# LeafCanV002.net
KiCad netlist of a schematic drawn in EAGLE
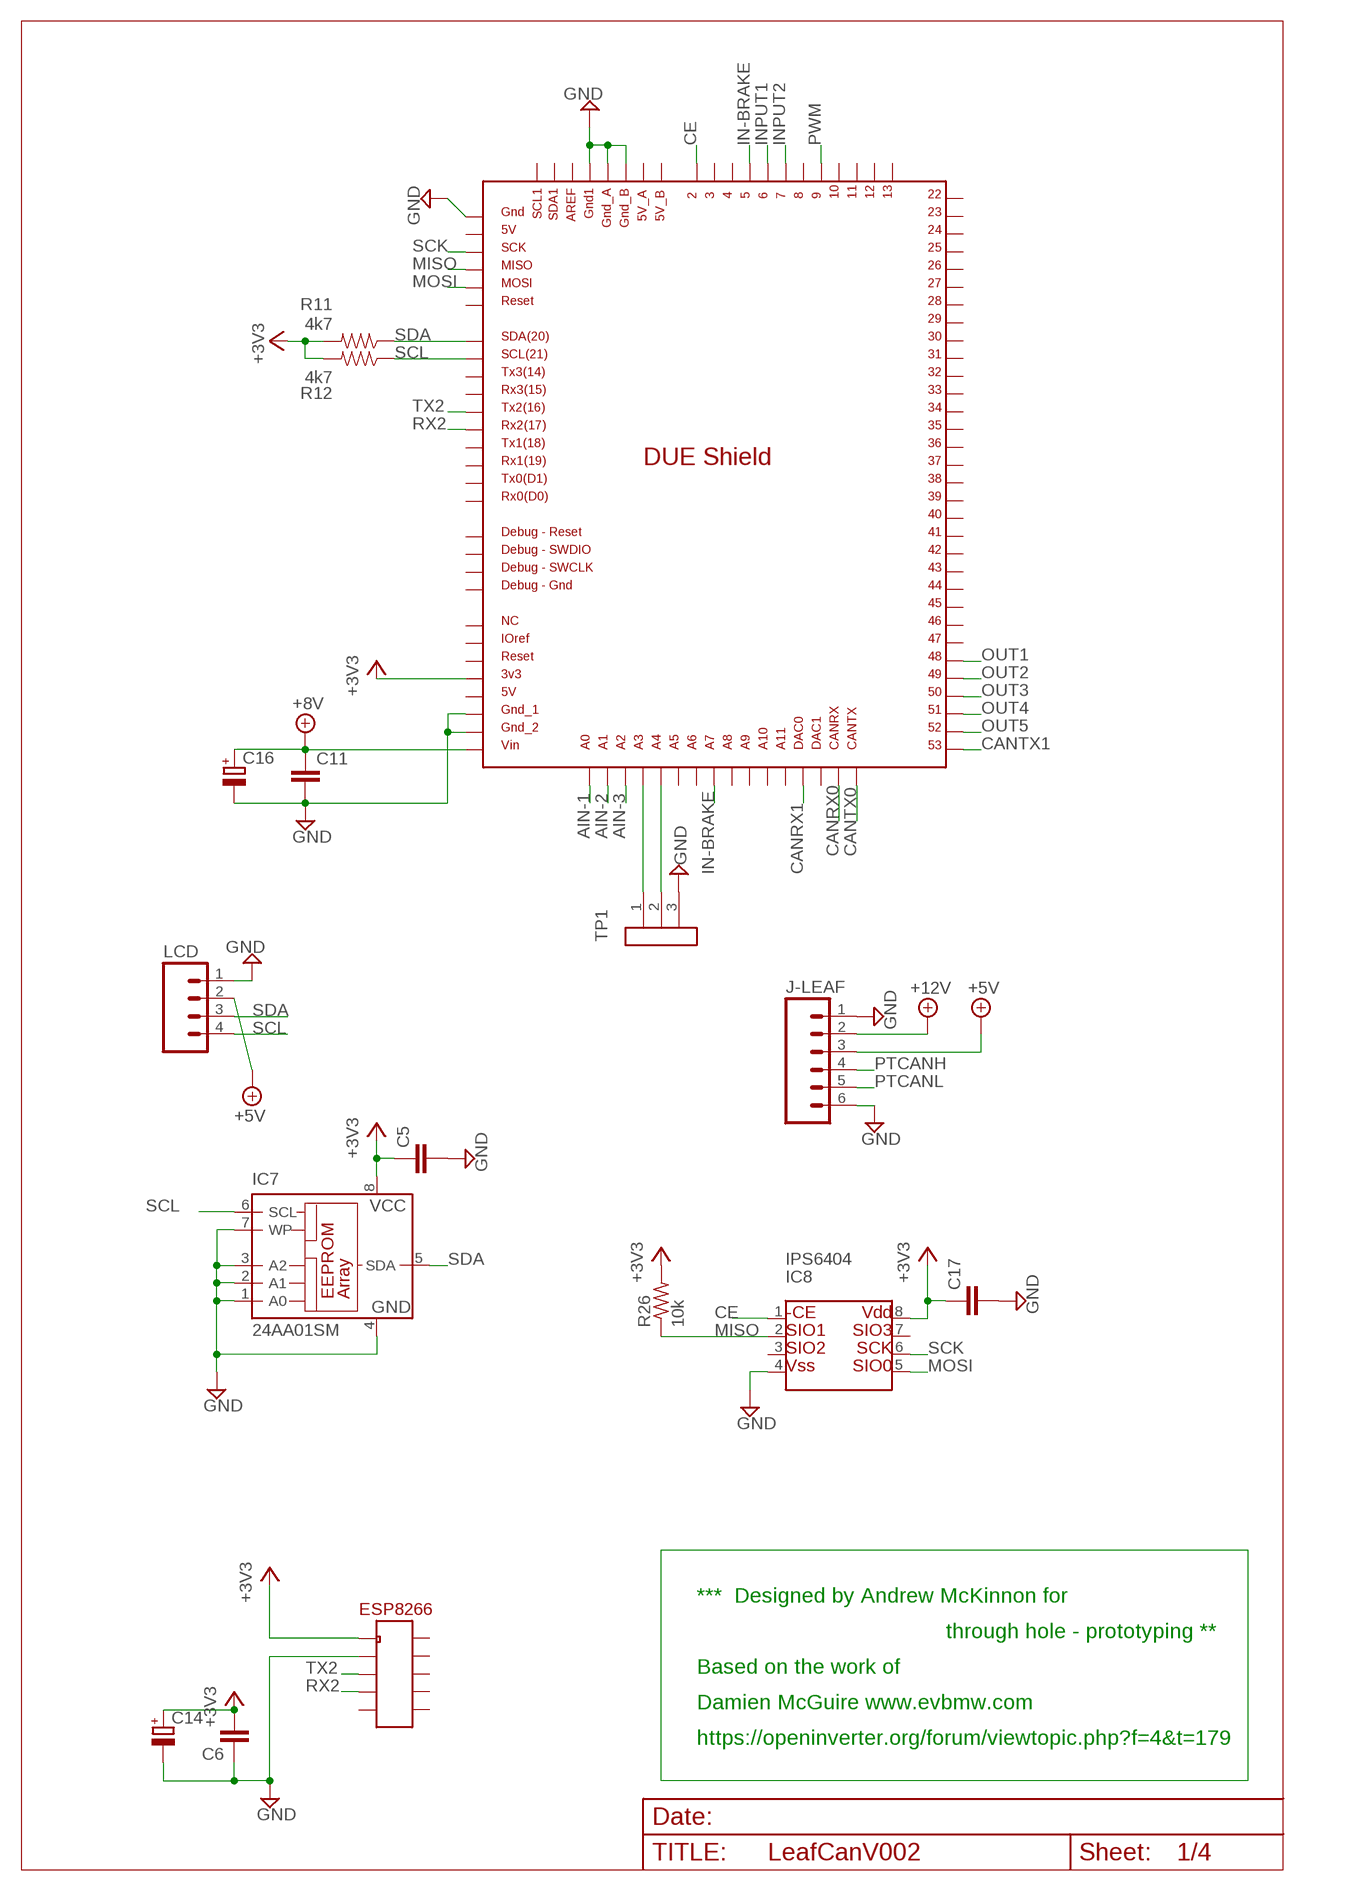
[diagram p0: schematic, sheet 1]
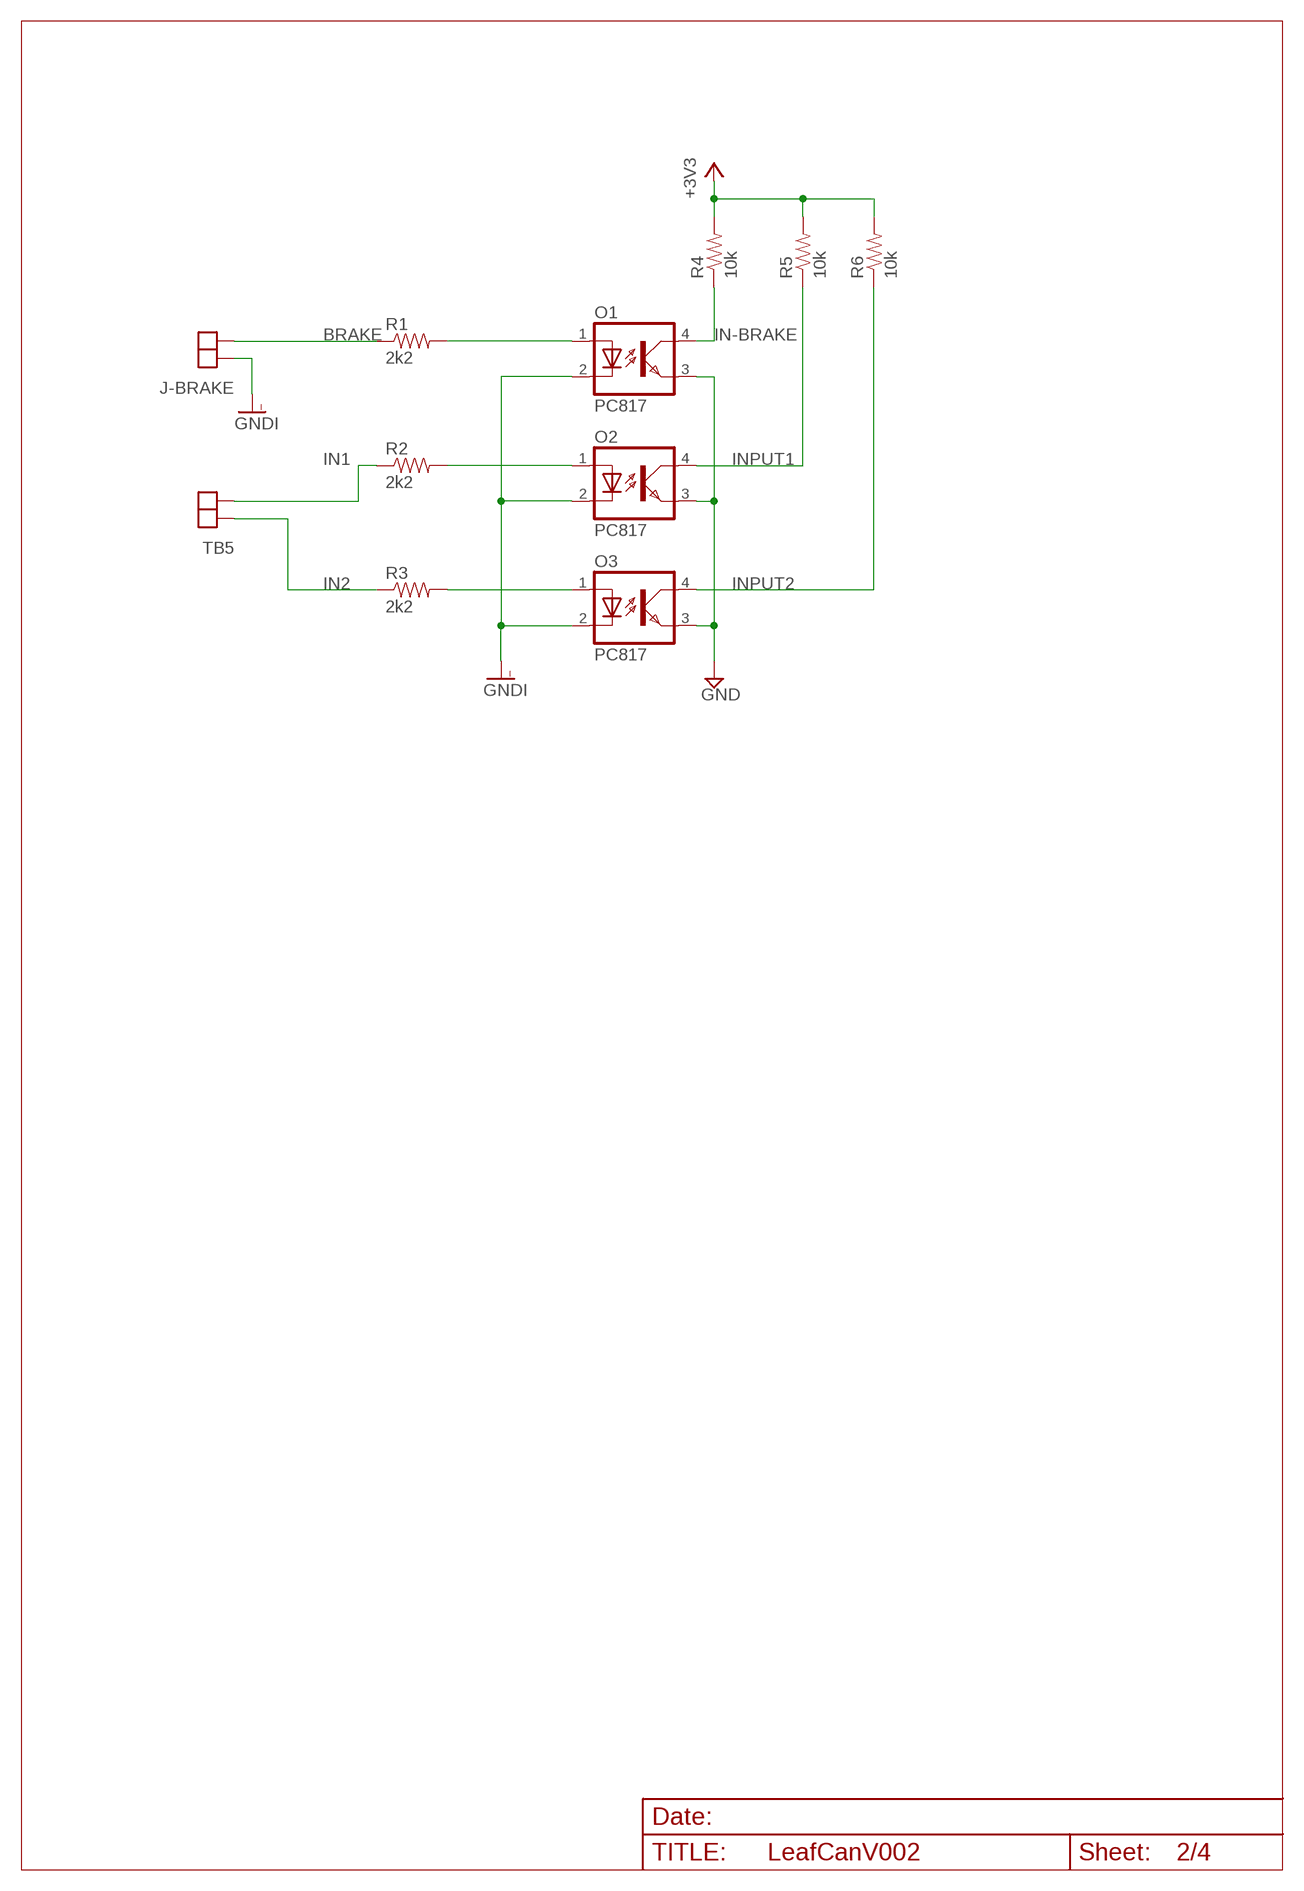
[diagram p1: schematic, sheet 2]
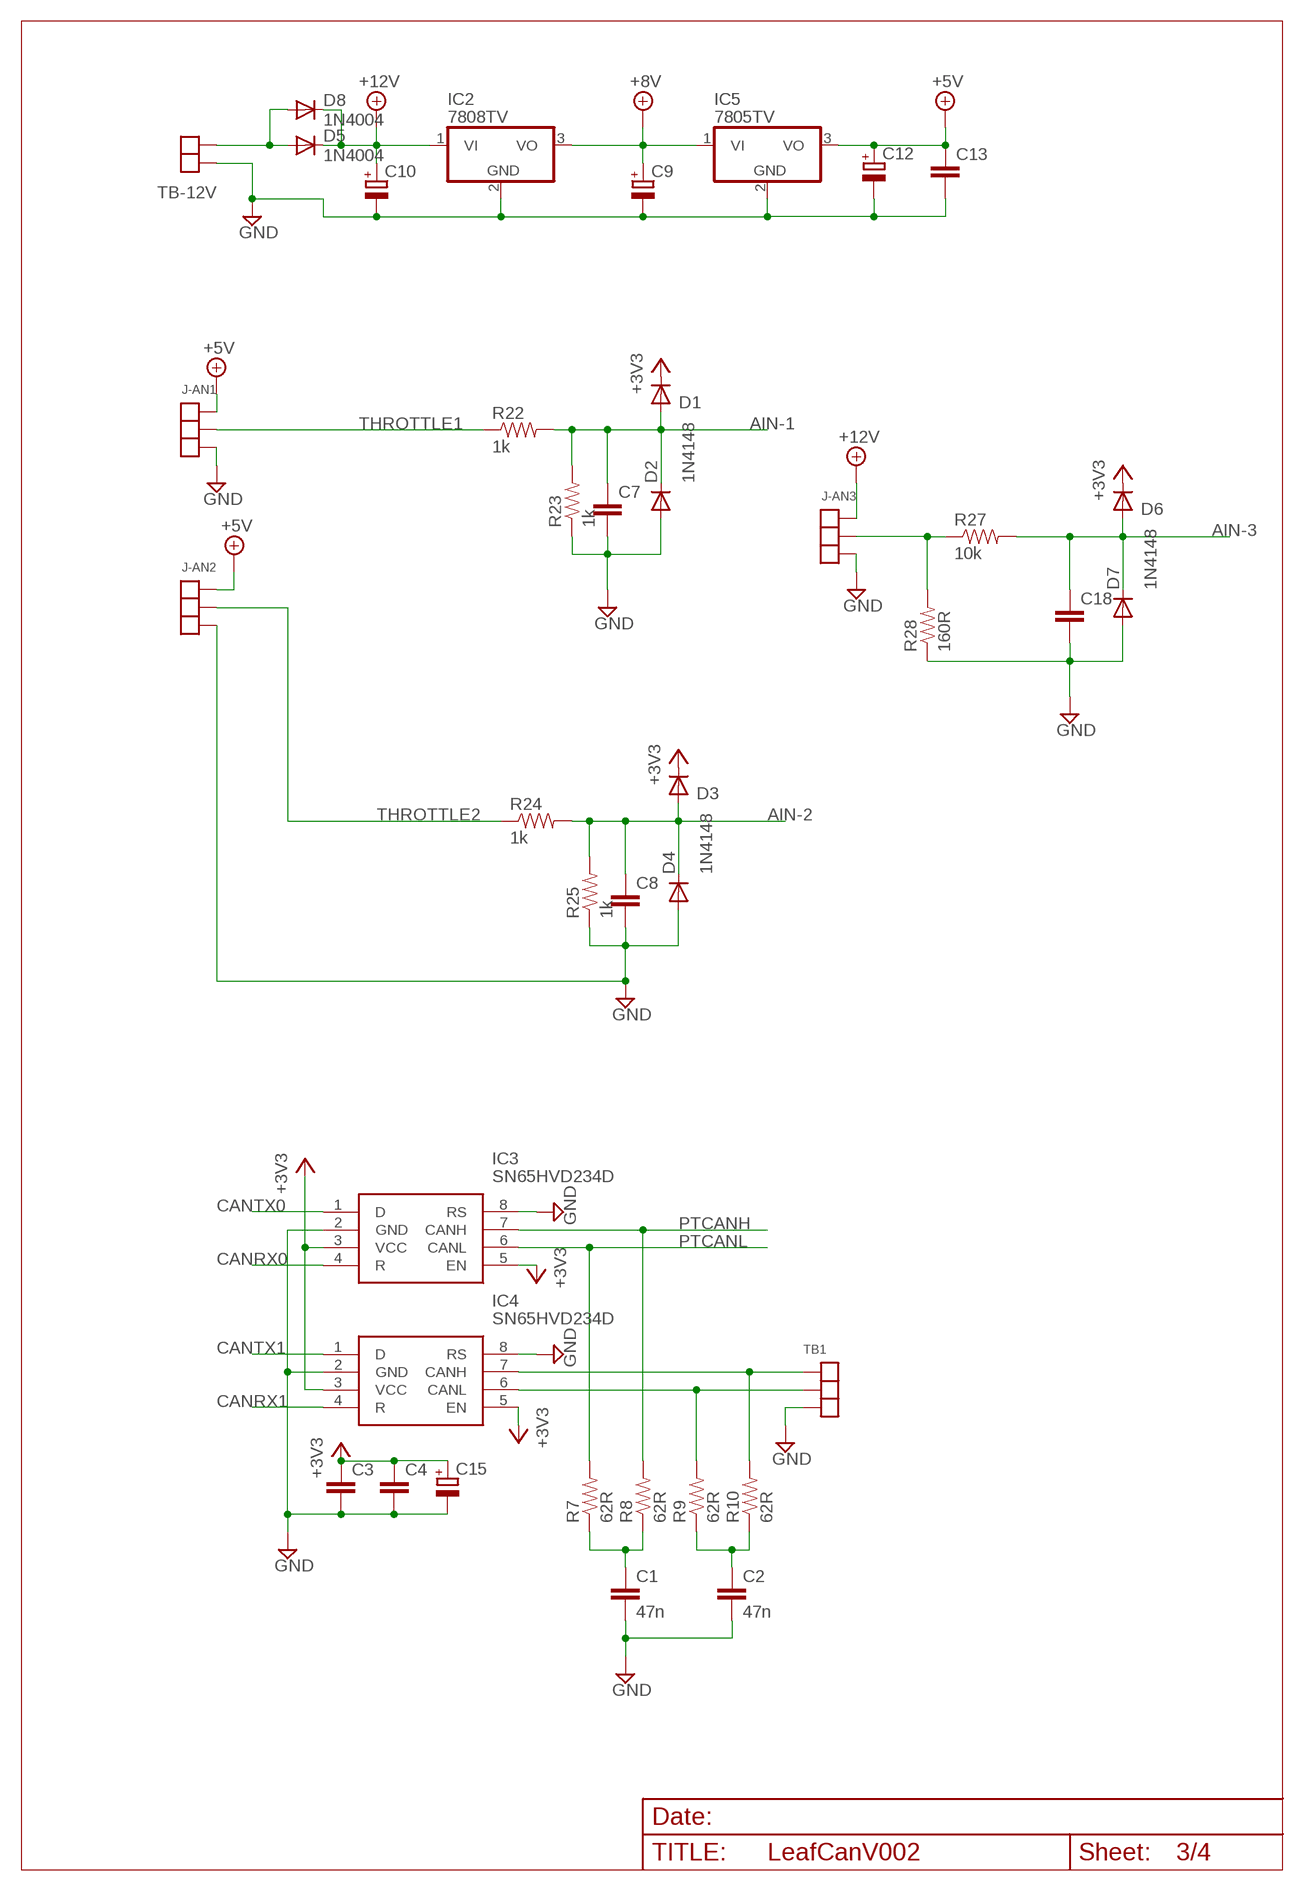
[diagram p2: schematic, sheet 3]
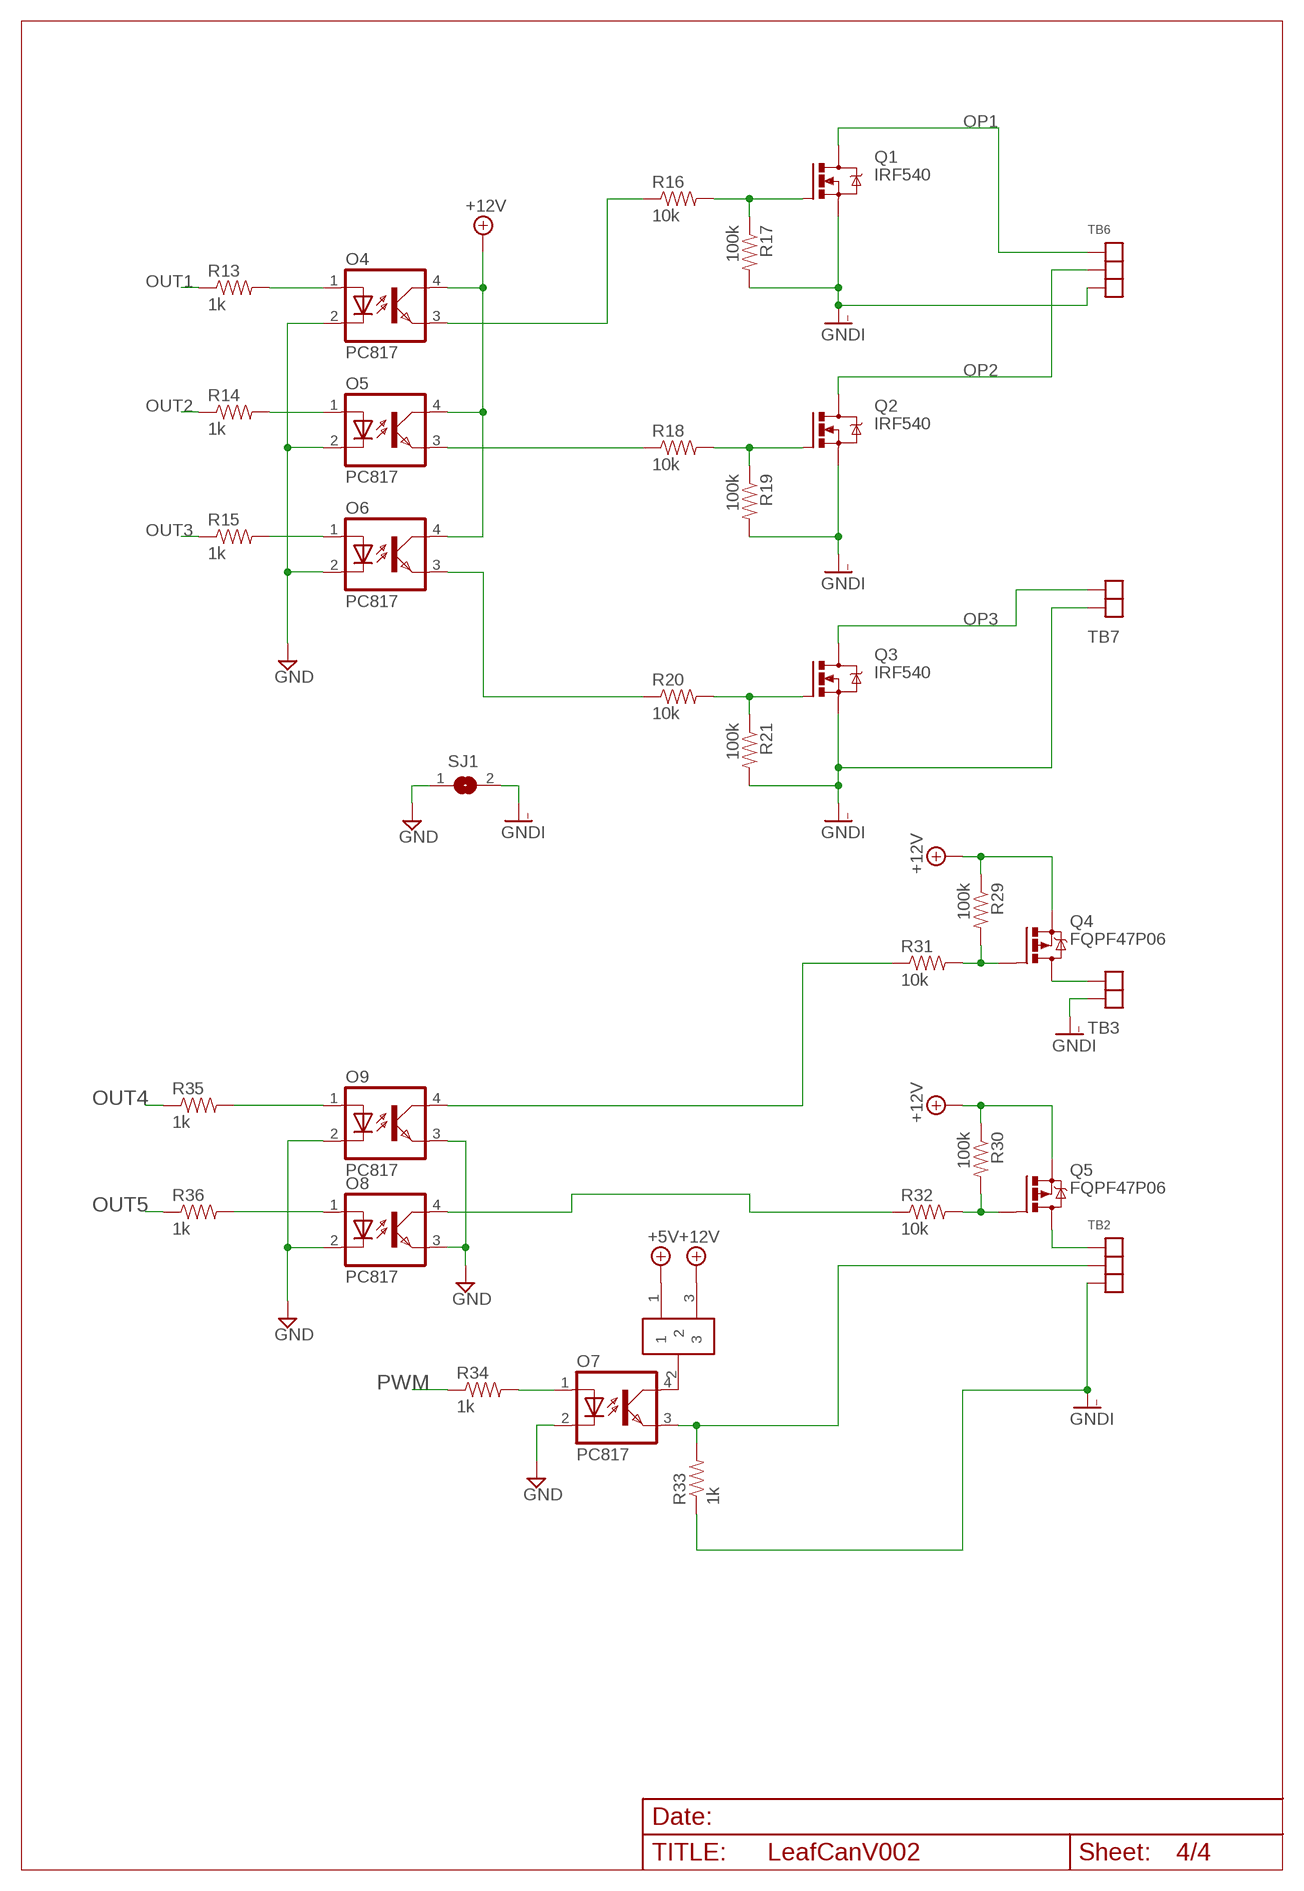
[diagram p3: schematic, sheet 4]

(export (version "E")
  (design (tool "Eeschema 10.0.6"))
  (components
    (comp (ref "C1")
      (value "47n")
      (footprint "eagle-import:C025-030X050")
      (libsource (lib "eagle-import") (part "C-EU025-030X050"))
    )
    (comp (ref "C2")
      (value "47n")
      (footprint "eagle-import:C025-030X050")
      (libsource (lib "eagle-import") (part "C-EU025-030X050"))
    )
    (comp (ref "C3")
      (value "BCAP")
      (footprint "eagle-import:BCAP")
      (libsource (lib "eagle-import") (part "BCAP"))
    )
    (comp (ref "C4")
      (value "BCAP")
      (footprint "eagle-import:BCAP")
      (libsource (lib "eagle-import") (part "BCAP"))
    )
    (comp (ref "C7")
      (value "BCAP")
      (footprint "eagle-import:BCAP")
      (libsource (lib "eagle-import") (part "BCAP"))
    )
    (comp (ref "C8")
      (value "BCAP")
      (footprint "eagle-import:BCAP")
      (libsource (lib "eagle-import") (part "BCAP"))
    )
    (comp (ref "C9")
      (value "C-RB200100")
      (footprint "eagle-import:CPOL-RADIAL-10UF-25V")
      (libsource (lib "eagle-import") (part "C-RB200100"))
    )
    (comp (ref "C10")
      (value "CPOL-EUE7.5-18")
      (footprint "eagle-import:E7,5-18")
      (libsource (lib "eagle-import") (part "CPOL-EUE7.5-18"))
    )
    (comp (ref "C12")
      (value "C-RB200100")
      (footprint "eagle-import:CPOL-RADIAL-10UF-25V")
      (libsource (lib "eagle-import") (part "C-RB200100"))
    )
    (comp (ref "C13")
      (value "BCAP")
      (footprint "eagle-import:BCAP")
      (libsource (lib "eagle-import") (part "BCAP"))
    )
    (comp (ref "C15")
      (value "C-RB200100")
      (footprint "eagle-import:CPOL-RADIAL-10UF-25V")
      (libsource (lib "eagle-import") (part "Andrew Passive_C-RB200100"))
    )
    (comp (ref "C18")
      (value "BCAP")
      (footprint "eagle-import:BCAP")
      (libsource (lib "eagle-import") (part "BCAP"))
    )
    (comp (ref "D1")
      (value "1N4148")
      (footprint "eagle-import:D3")
      (libsource (lib "eagle-import") (part "1N4148DO35-7"))
    )
    (comp (ref "D2")
      (value "1N4148")
      (footprint "eagle-import:D3")
      (libsource (lib "eagle-import") (part "1N4148DO35-7"))
    )
    (comp (ref "D3")
      (value "1N4148")
      (footprint "eagle-import:D3")
      (libsource (lib "eagle-import") (part "1N4148DO35-7"))
    )
    (comp (ref "D4")
      (value "1N4148")
      (footprint "eagle-import:D3")
      (libsource (lib "eagle-import") (part "1N4148DO35-7"))
    )
    (comp (ref "D5")
      (value "1N4004")
      (footprint "eagle-import:DO41-10")
      (libsource (lib "eagle-import") (part "1N4004"))
    )
    (comp (ref "D6")
      (value "1N4148")
      (footprint "eagle-import:D3")
      (libsource (lib "eagle-import") (part "1N4148DO35-7"))
    )
    (comp (ref "D7")
      (value "1N4148")
      (footprint "eagle-import:D3")
      (libsource (lib "eagle-import") (part "1N4148DO35-7"))
    )
    (comp (ref "D8")
      (value "1N4004")
      (footprint "eagle-import:DO41-10")
      (libsource (lib "eagle-import") (part "1N4004"))
    )
    (comp (ref "IC2")
      (value "7808TV")
      (footprint "eagle-import:TO220V")
      (libsource (lib "eagle-import") (part "78TV08"))
    )
    (comp (ref "IC3")
      (value "SN65HVD234D")
      (footprint "eagle-import:SOIC127P600X175-8N")
      (fields
        (field (name "MOUSER_PART_NUMBER") "595-SN65HVD234D")
        (field (name "RS_PART_NUMBER") "6624315P")
      )
      (libsource (lib "eagle-import") (part "SN65HVD234D"))
    )
    (comp (ref "IC4")
      (value "SN65HVD234D")
      (footprint "eagle-import:SOIC127P600X175-8N")
      (fields
        (field (name "MOUSER_PART_NUMBER") "595-SN65HVD234D")
        (field (name "RS_PART_NUMBER") "6624315P")
      )
      (libsource (lib "eagle-import") (part "SN65HVD234D"))
    )
    (comp (ref "IC5")
      (value "7805TV")
      (footprint "eagle-import:TO220V")
      (libsource (lib "eagle-import") (part "78TV05"))
    )
    (comp (ref "J-AN1")
      (value "TB3381V")
      (footprint "eagle-import:TB-KF2EDG381-3-V")
      (libsource (lib "eagle-import") (part "TB3381V"))
    )
    (comp (ref "J-AN2")
      (value "TB3381V")
      (footprint "eagle-import:TB-KF2EDG381-3-V")
      (libsource (lib "eagle-import") (part "TB3381V"))
    )
    (comp (ref "J-AN3")
      (value "TB3381V")
      (footprint "eagle-import:TB-KF2EDG381-3-V")
      (libsource (lib "eagle-import") (part "TB3381V"))
    )
    (comp (ref "R7")
      (value "62R")
      (footprint "eagle-import:AXIAL-0.4")
      (libsource (lib "eagle-import") (part "R4"))
    )
    (comp (ref "R8")
      (value "62R")
      (footprint "eagle-import:AXIAL-0.4")
      (libsource (lib "eagle-import") (part "R4"))
    )
    (comp (ref "R9")
      (value "62R")
      (footprint "eagle-import:AXIAL-0.4")
      (libsource (lib "eagle-import") (part "R4"))
    )
    (comp (ref "R10")
      (value "62R")
      (footprint "eagle-import:AXIAL-0.4")
      (libsource (lib "eagle-import") (part "R4"))
    )
    (comp (ref "R22")
      (value "1k")
      (footprint "eagle-import:AXIAL-0.4")
      (libsource (lib "eagle-import") (part "R4"))
    )
    (comp (ref "R23")
      (value "1k")
      (footprint "eagle-import:AXIAL-0.4")
      (libsource (lib "eagle-import") (part "R4"))
    )
    (comp (ref "R24")
      (value "1k")
      (footprint "eagle-import:AXIAL-0.4")
      (libsource (lib "eagle-import") (part "R4"))
    )
    (comp (ref "R25")
      (value "1k")
      (footprint "eagle-import:AXIAL-0.4")
      (libsource (lib "eagle-import") (part "R4"))
    )
    (comp (ref "R27")
      (value "10k")
      (footprint "eagle-import:AXIAL-0.4")
      (libsource (lib "eagle-import") (part "R4"))
    )
    (comp (ref "R28")
      (value "160R")
      (footprint "eagle-import:AXIAL-0.4")
      (libsource (lib "eagle-import") (part "R4"))
    )
    (comp (ref "TB-12V")
      (value "TB2381")
      (footprint "eagle-import:TB-KF2EDG381-2P")
      (libsource (lib "eagle-import") (part "TB2381"))
    )
    (comp (ref "TB1")
      (value "TB3381V")
      (footprint "eagle-import:TB-KF2EDG381-3-V")
      (libsource (lib "eagle-import") (part "TB3381V"))
    )
    (comp (ref "JP1")
      (value "JP1X3")
      (footprint "eagle-import:JP1X3")
      (libsource (lib "eagle-import") (part "JP1X3"))
    )
    (comp (ref "O4")
      (value "PC817")
      (footprint "eagle-import:DIL04")
      (fields (field (name "MPN") "PC817X4J000F"))
      (libsource (lib "eagle-import") (part "PC817"))
    )
    (comp (ref "O5")
      (value "PC817")
      (footprint "eagle-import:DIL04")
      (fields (field (name "MPN") "PC817X4J000F"))
      (libsource (lib "eagle-import") (part "PC817"))
    )
    (comp (ref "O6")
      (value "PC817")
      (footprint "eagle-import:DIL04")
      (fields (field (name "MPN") "PC817X4J000F"))
      (libsource (lib "eagle-import") (part "PC817"))
    )
    (comp (ref "O7")
      (value "PC817")
      (footprint "eagle-import:DIL04")
      (fields (field (name "MPN") "PC817X4J000F"))
      (libsource (lib "eagle-import") (part "PC817"))
    )
    (comp (ref "O8")
      (value "PC817")
      (footprint "eagle-import:DIL04")
      (fields
        (field (name "MPN") "PC817X4J000F")
        (field (name "MPN_1") "PC817X4J000F")
        (field (name "OC_FARNELL") "9707727")
        (field (name "OC_NEWARK") "97K7059")
      )
      (libsource (lib "eagle-import") (part "PC817"))
    )
    (comp (ref "O9")
      (value "PC817")
      (footprint "eagle-import:DIL04")
      (fields
        (field (name "MPN") "PC817X4J000F")
        (field (name "MPN_1") "PC817X4J000F")
        (field (name "OC_FARNELL") "9707727")
        (field (name "OC_NEWARK") "97K7059")
      )
      (libsource (lib "eagle-import") (part "PC817"))
    )
    (comp (ref "Q1")
      (value "IRF540")
      (footprint "eagle-import:TO220BV")
      (libsource (lib "eagle-import") (part "IRF540"))
    )
    (comp (ref "Q2")
      (value "IRF540")
      (footprint "eagle-import:TO220BV")
      (libsource (lib "eagle-import") (part "IRF540"))
    )
    (comp (ref "Q3")
      (value "IRF540")
      (footprint "eagle-import:TO220BV")
      (libsource (lib "eagle-import") (part "IRF540"))
    )
    (comp (ref "Q4")
      (value "FQPF47P06")
      (footprint "eagle-import:TO220BV")
      (libsource (lib "eagle-import") (part "MOSFET-PCHFQPF47P06"))
    )
    (comp (ref "Q5")
      (value "FQPF47P06")
      (footprint "eagle-import:TO220BV")
      (libsource (lib "eagle-import") (part "MOSFET-PCHFQPF47P06"))
    )
    (comp (ref "R13")
      (value "1k")
      (footprint "eagle-import:AXIAL-0.4")
      (libsource (lib "eagle-import") (part "R4"))
    )
    (comp (ref "R14")
      (value "1k")
      (footprint "eagle-import:AXIAL-0.4")
      (libsource (lib "eagle-import") (part "R4"))
    )
    (comp (ref "R15")
      (value "1k")
      (footprint "eagle-import:AXIAL-0.4")
      (libsource (lib "eagle-import") (part "R4"))
    )
    (comp (ref "R16")
      (value "10k")
      (footprint "eagle-import:AXIAL-0.4")
      (libsource (lib "eagle-import") (part "R4"))
    )
    (comp (ref "R17")
      (value "100k")
      (footprint "eagle-import:AXIAL-0.4")
      (libsource (lib "eagle-import") (part "R4"))
    )
    (comp (ref "R18")
      (value "10k")
      (footprint "eagle-import:AXIAL-0.4")
      (libsource (lib "eagle-import") (part "R4"))
    )
    (comp (ref "R19")
      (value "100k")
      (footprint "eagle-import:AXIAL-0.4")
      (libsource (lib "eagle-import") (part "R4"))
    )
    (comp (ref "R20")
      (value "10k")
      (footprint "eagle-import:AXIAL-0.4")
      (libsource (lib "eagle-import") (part "R4"))
    )
    (comp (ref "R21")
      (value "100k")
      (footprint "eagle-import:AXIAL-0.4")
      (libsource (lib "eagle-import") (part "R4"))
    )
    (comp (ref "R29")
      (value "100k")
      (footprint "eagle-import:AXIAL-0.4")
      (libsource (lib "eagle-import") (part "R4"))
    )
    (comp (ref "R30")
      (value "100k")
      (footprint "eagle-import:AXIAL-0.4")
      (libsource (lib "eagle-import") (part "R4"))
    )
    (comp (ref "R31")
      (value "10k")
      (footprint "eagle-import:AXIAL-0.4")
      (libsource (lib "eagle-import") (part "R4"))
    )
    (comp (ref "R32")
      (value "10k")
      (footprint "eagle-import:AXIAL-0.4")
      (libsource (lib "eagle-import") (part "R4"))
    )
    (comp (ref "R33")
      (value "1k")
      (footprint "eagle-import:AXIAL-0.4")
      (libsource (lib "eagle-import") (part "R4"))
    )
    (comp (ref "R34")
      (value "1k")
      (footprint "eagle-import:AXIAL-0.4")
      (libsource (lib "eagle-import") (part "R4"))
    )
    (comp (ref "R35")
      (value "1k")
      (footprint "eagle-import:AXIAL-0.4")
      (libsource (lib "eagle-import") (part "R4"))
    )
    (comp (ref "R36")
      (value "1k")
      (footprint "eagle-import:AXIAL-0.4")
      (libsource (lib "eagle-import") (part "R4"))
    )
    (comp (ref "SJ1") (value "SJ") (footprint "eagle-import:SJ") (libsource (lib "eagle-import") (part "SJ")))
    (comp (ref "TB2")
      (value "TB3381")
      (footprint "eagle-import:TB-KF2EDG381-3P")
      (libsource (lib "eagle-import") (part "TB3381"))
    )
    (comp (ref "TB3")
      (value "TB2381")
      (footprint "eagle-import:TB-KF2EDG381-2P")
      (libsource (lib "eagle-import") (part "TB2381"))
    )
    (comp (ref "TB6")
      (value "TB3381")
      (footprint "eagle-import:TB-KF2EDG381-3P")
      (libsource (lib "eagle-import") (part "TB3381"))
    )
    (comp (ref "TB7")
      (value "TB2381")
      (footprint "eagle-import:TB-KF2EDG381-2P")
      (libsource (lib "eagle-import") (part "TB2381"))
    )
    (comp (ref "J-BRAKE")
      (value "TB2381")
      (footprint "eagle-import:TB-KF2EDG381-2P")
      (libsource (lib "eagle-import") (part "TB2381"))
    )
    (comp (ref "O1")
      (value "PC817")
      (footprint "eagle-import:DIL04")
      (fields (field (name "MPN") "PC817X4J000F"))
      (libsource (lib "eagle-import") (part "PC817"))
    )
    (comp (ref "O2")
      (value "PC817")
      (footprint "eagle-import:DIL04")
      (fields (field (name "MPN") "PC817X4J000F"))
      (libsource (lib "eagle-import") (part "PC817"))
    )
    (comp (ref "O3")
      (value "PC817")
      (footprint "eagle-import:DIL04")
      (fields (field (name "MPN") "PC817X4J000F"))
      (libsource (lib "eagle-import") (part "PC817"))
    )
    (comp (ref "R1")
      (value "2k2")
      (footprint "eagle-import:AXIAL-0.4")
      (libsource (lib "eagle-import") (part "R4"))
    )
    (comp (ref "R2")
      (value "2k2")
      (footprint "eagle-import:AXIAL-0.4")
      (libsource (lib "eagle-import") (part "R4"))
    )
    (comp (ref "R3")
      (value "2k2")
      (footprint "eagle-import:AXIAL-0.4")
      (libsource (lib "eagle-import") (part "R4"))
    )
    (comp (ref "R4")
      (value "10k")
      (footprint "eagle-import:AXIAL-0.4")
      (libsource (lib "eagle-import") (part "R4"))
    )
    (comp (ref "R5")
      (value "10k")
      (footprint "eagle-import:AXIAL-0.4")
      (libsource (lib "eagle-import") (part "R4"))
    )
    (comp (ref "R6")
      (value "10k")
      (footprint "eagle-import:AXIAL-0.4")
      (libsource (lib "eagle-import") (part "R4"))
    )
    (comp (ref "TB5")
      (value "TB2381")
      (footprint "eagle-import:TB-KF2EDG381-2P")
      (libsource (lib "eagle-import") (part "TB2381"))
    )
    (comp (ref "C5")
      (value "BCAP")
      (footprint "eagle-import:BCAP")
      (libsource (lib "eagle-import") (part "BCAP"))
    )
    (comp (ref "C6")
      (value "BCAP")
      (footprint "eagle-import:BCAP")
      (libsource (lib "eagle-import") (part "BCAP"))
    )
    (comp (ref "C11")
      (value "BCAP")
      (footprint "eagle-import:BCAP")
      (libsource (lib "eagle-import") (part "BCAP"))
    )
    (comp (ref "C14")
      (value "C-RB200100")
      (footprint "eagle-import:CPOL-RADIAL-10UF-25V")
      (libsource (lib "eagle-import") (part "Andrew Passive_C-RB200100"))
    )
    (comp (ref "C16")
      (value "C-RB200100")
      (footprint "eagle-import:CPOL-RADIAL-10UF-25V")
      (libsource (lib "eagle-import") (part "Andrew Passive_C-RB200100"))
    )
    (comp (ref "C17")
      (value "BCAP")
      (footprint "eagle-import:BCAP")
      (libsource (lib "eagle-import") (part "BCAP"))
    )
    (comp (ref "ESP8266")
      (value "IDC10")
      (footprint "eagle-import:IDC10-SMALL")
      (libsource (lib "eagle-import") (part "IDC10"))
    )
    (comp (ref "IC1")
      (value "DUE(NORMAL)")
      (footprint "eagle-import:DUE(NORMAL)")
      (libsource (lib "eagle-import") (part "DUE(NORMAL)"))
    )
    (comp (ref "IC7")
      (value "24AA01SM")
      (footprint "eagle-import:SO-08M")
      (fields (field (name "MF") "MICROCHIP") (field (name "MPN") "24AA01-I/SN"))
      (libsource (lib "eagle-import") (part "24SMAA01"))
    )
    (comp (ref "IC8")
      (value "IPS6404")
      (footprint "eagle-import:SO-08")
      (libsource (lib "eagle-import") (part "IPS6404"))
    )
    (comp (ref "J-LEAF")
      (value "MO6POL")
      (footprint "eagle-import:MOLEX-6")
      (libsource (lib "eagle-import") (part "MO6POL"))
    )
    (comp (ref "LCD")
      (value "MO4POL")
      (footprint "eagle-import:MOLEX-4")
      (libsource (lib "eagle-import") (part "MO4POL"))
    )
    (comp (ref "R11")
      (value "4k7")
      (footprint "eagle-import:AXIAL-0.4")
      (libsource (lib "eagle-import") (part "R4"))
    )
    (comp (ref "R12")
      (value "4k7")
      (footprint "eagle-import:AXIAL-0.4")
      (libsource (lib "eagle-import") (part "R4"))
    )
    (comp (ref "R26")
      (value "10k")
      (footprint "eagle-import:R1206")
      (libsource (lib "eagle-import") (part "R-US_R1206"))
    )
    (comp (ref "TP1")
      (value "SIL3")
      (footprint "eagle-import:SIL3")
      (libsource (lib "eagle-import") (part "SIL3"))
    )
  )
  (nets
    (net (code "1") (name "+3V3") (class "Default")
      (node (ref "C14") (pin "1") (pinfunction "+_1") (pintype "passive"))
      (node (ref "C15") (pin "1") (pinfunction "+_1") (pintype "passive"))
      (node (ref "C17") (pin "1") (pinfunction "1_1") (pintype "passive"))
      (node (ref "C3") (pin "1") (pinfunction "1_1") (pintype "passive"))
      (node (ref "C4") (pin "1") (pinfunction "1_1") (pintype "passive"))
      (node (ref "C5") (pin "1") (pinfunction "1_1") (pintype "passive"))
      (node (ref "C6") (pin "2") (pinfunction "2_2") (pintype "passive"))
      (node (ref "D1") (pin "C") (pinfunction "C_C") (pintype "passive"))
      (node (ref "D3") (pin "C") (pinfunction "C_C") (pintype "passive"))
      (node (ref "D6") (pin "C") (pinfunction "C_C") (pintype "passive"))
      (node (ref "ESP8266") (pin "1") (pinfunction "1_1") (pintype "bidirectional"))
      (node (ref "IC1") (pin "3V3") (pinfunction "3V3_3V3") (pintype "bidirectional"))
      (node (ref "IC3") (pin "3") (pinfunction "VCC_3") (pintype "bidirectional"))
      (node (ref "IC3") (pin "5") (pinfunction "EN_5") (pintype "bidirectional"))
      (node (ref "IC4") (pin "3") (pinfunction "VCC_3") (pintype "bidirectional"))
      (node (ref "IC4") (pin "5") (pinfunction "EN_5") (pintype "bidirectional"))
      (node (ref "IC7") (pin "8") (pinfunction "VCC_8") (pintype "power_in"))
      (node (ref "IC8") (pin "8") (pinfunction "P$8_8") (pintype "bidirectional"))
      (node (ref "R11") (pin "P$2") (pinfunction "2_P$2") (pintype "passive"))
      (node (ref "R12") (pin "P$2") (pinfunction "2_P$2") (pintype "passive"))
      (node (ref "R26") (pin "2") (pinfunction "2_2") (pintype "passive"))
      (node (ref "R4") (pin "P$2") (pinfunction "2_P$2") (pintype "passive"))
      (node (ref "R5") (pin "P$2") (pinfunction "2_P$2") (pintype "passive"))
      (node (ref "R6") (pin "P$2") (pinfunction "2_P$2") (pintype "passive"))
    )
    (net (code "2") (name "+5V") (class "Default")
      (node (ref "C12") (pin "1") (pinfunction "+_1") (pintype "passive"))
      (node (ref "C13") (pin "1") (pinfunction "1_1") (pintype "passive"))
      (node (ref "IC5") (pin "3") (pinfunction "VO_3") (pintype "passive"))
      (node (ref "J-AN1") (pin "1") (pinfunction "1_1") (pintype "bidirectional"))
      (node (ref "J-AN2") (pin "1") (pinfunction "1_1") (pintype "bidirectional"))
      (node (ref "J-LEAF") (pin "3") (pinfunction "3_3") (pintype "passive"))
      (node (ref "JP1") (pin "1") (pinfunction "1_1") (pintype "bidirectional"))
      (node (ref "LCD") (pin "2") (pinfunction "2_2") (pintype "passive"))
    )
    (net (code "3") (name "+8V") (class "Default")
      (node (ref "C11") (pin "1") (pinfunction "1_1") (pintype "passive"))
      (node (ref "C16") (pin "1") (pinfunction "+_1") (pintype "passive"))
      (node (ref "C9") (pin "1") (pinfunction "+_1") (pintype "passive"))
      (node (ref "IC1") (pin "VIN") (pinfunction "VIN_VIN") (pintype "bidirectional"))
      (node (ref "IC2") (pin "3") (pinfunction "VO_3") (pintype "passive"))
      (node (ref "IC5") (pin "1") (pinfunction "VI_1") (pintype "input"))
    )
    (net (code "4") (name "+12V") (class "Default")
      (node (ref "C10") (pin "+") (pinfunction "+_+") (pintype "passive"))
      (node (ref "D5") (pin "C") (pinfunction "C_C") (pintype "passive"))
      (node (ref "D8") (pin "C") (pinfunction "C_C") (pintype "passive"))
      (node (ref "IC2") (pin "1") (pinfunction "VI_1") (pintype "input"))
      (node (ref "J-AN3") (pin "1") (pinfunction "1_1") (pintype "bidirectional"))
      (node (ref "J-LEAF") (pin "2") (pinfunction "2_2") (pintype "passive"))
      (node (ref "JP1") (pin "3") (pinfunction "3_3") (pintype "bidirectional"))
      (node (ref "O4") (pin "4") (pinfunction "COL_4") (pintype "passive"))
      (node (ref "O5") (pin "4") (pinfunction "COL_4") (pintype "passive"))
      (node (ref "O6") (pin "4") (pinfunction "COL_4") (pintype "passive"))
      (node (ref "Q4") (pin "S") (pinfunction "S_S") (pintype "passive"))
      (node (ref "Q5") (pin "S") (pinfunction "S_S") (pintype "passive"))
      (node (ref "R29") (pin "P$1") (pinfunction "1_P$1") (pintype "passive"))
      (node (ref "R30") (pin "P$1") (pinfunction "1_P$1") (pintype "passive"))
    )
    (net (code "5") (name "AIN-1") (class "Default")
      (node (ref "C7") (pin "1") (pinfunction "1_1") (pintype "passive"))
      (node (ref "D1") (pin "A") (pinfunction "A_A") (pintype "passive"))
      (node (ref "D2") (pin "C") (pinfunction "C_C") (pintype "passive"))
      (node (ref "IC1") (pin "A0") (pinfunction "A0_A0") (pintype "bidirectional"))
      (node (ref "R22") (pin "P$2") (pinfunction "2_P$2") (pintype "passive"))
      (node (ref "R23") (pin "P$2") (pinfunction "2_P$2") (pintype "passive"))
    )
    (net (code "6") (name "AIN-2") (class "Default")
      (node (ref "C8") (pin "1") (pinfunction "1_1") (pintype "passive"))
      (node (ref "D3") (pin "A") (pinfunction "A_A") (pintype "passive"))
      (node (ref "D4") (pin "C") (pinfunction "C_C") (pintype "passive"))
      (node (ref "IC1") (pin "A1") (pinfunction "A1_A1") (pintype "bidirectional"))
      (node (ref "R24") (pin "P$2") (pinfunction "2_P$2") (pintype "passive"))
      (node (ref "R25") (pin "P$2") (pinfunction "2_P$2") (pintype "passive"))
    )
    (net (code "7") (name "AIN-3") (class "Default")
      (node (ref "C18") (pin "1") (pinfunction "1_1") (pintype "passive"))
      (node (ref "D6") (pin "A") (pinfunction "A_A") (pintype "passive"))
      (node (ref "D7") (pin "C") (pinfunction "C_C") (pintype "passive"))
      (node (ref "IC1") (pin "A2") (pinfunction "A2_A2") (pintype "bidirectional"))
      (node (ref "R27") (pin "P$2") (pinfunction "2_P$2") (pintype "passive"))
    )
    (net (code "8") (name "BRAKE") (class "Default")
      (node (ref "J-BRAKE") (pin "1") (pinfunction "1_1") (pintype "bidirectional"))
      (node (ref "R1") (pin "P$1") (pinfunction "1_P$1") (pintype "passive"))
    )
    (net (code "9") (name "CANRX0") (class "Default")
      (node (ref "IC1") (pin "CANRX") (pinfunction "CANRX_CANRX") (pintype "bidirectional"))
      (node (ref "IC3") (pin "4") (pinfunction "R_4") (pintype "bidirectional"))
    )
    (net (code "10") (name "CANRX1") (class "Default")
      (node (ref "IC1") (pin "DAC0") (pinfunction "DAC0_DAC0") (pintype "bidirectional"))
      (node (ref "IC4") (pin "4") (pinfunction "R_4") (pintype "bidirectional"))
    )
    (net (code "11") (name "CANTX0") (class "Default")
      (node (ref "IC1") (pin "CANTX") (pinfunction "CANTX_CANTX") (pintype "bidirectional"))
      (node (ref "IC3") (pin "1") (pinfunction "D_1") (pintype "bidirectional"))
    )
    (net (code "12") (name "CANTX1") (class "Default")
      (node (ref "IC1") (pin "53") (pinfunction "53_53") (pintype "bidirectional"))
      (node (ref "IC4") (pin "1") (pinfunction "D_1") (pintype "bidirectional"))
    )
    (net (code "13") (name "CE") (class "Default")
      (node (ref "IC1") (pin "2") (pinfunction "2_2") (pintype "bidirectional"))
      (node (ref "IC8") (pin "1") (pinfunction "P$1_1") (pintype "bidirectional"))
    )
    (net (code "14") (name "GND") (class "Default")
      (node (ref "C1") (pin "2") (pinfunction "2_2") (pintype "passive"))
      (node (ref "C10") (pin "-") (pinfunction "-_-") (pintype "passive"))
      (node (ref "C11") (pin "2") (pinfunction "2_2") (pintype "passive"))
      (node (ref "C12") (pin "2") (pinfunction "-_2") (pintype "passive"))
      (node (ref "C13") (pin "2") (pinfunction "2_2") (pintype "passive"))
      (node (ref "C14") (pin "2") (pinfunction "-_2") (pintype "passive"))
      (node (ref "C15") (pin "2") (pinfunction "-_2") (pintype "passive"))
      (node (ref "C16") (pin "2") (pinfunction "-_2") (pintype "passive"))
      (node (ref "C17") (pin "2") (pinfunction "2_2") (pintype "passive"))
      (node (ref "C18") (pin "2") (pinfunction "2_2") (pintype "passive"))
      (node (ref "C2") (pin "2") (pinfunction "2_2") (pintype "passive"))
      (node (ref "C3") (pin "2") (pinfunction "2_2") (pintype "passive"))
      (node (ref "C4") (pin "2") (pinfunction "2_2") (pintype "passive"))
      (node (ref "C5") (pin "2") (pinfunction "2_2") (pintype "passive"))
      (node (ref "C6") (pin "1") (pinfunction "1_1") (pintype "passive"))
      (node (ref "C7") (pin "2") (pinfunction "2_2") (pintype "passive"))
      (node (ref "C8") (pin "2") (pinfunction "2_2") (pintype "passive"))
      (node (ref "C9") (pin "2") (pinfunction "-_2") (pintype "passive"))
      (node (ref "D2") (pin "A") (pinfunction "A_A") (pintype "passive"))
      (node (ref "D4") (pin "A") (pinfunction "A_A") (pintype "passive"))
      (node (ref "D7") (pin "A") (pinfunction "A_A") (pintype "passive"))
      (node (ref "ESP8266") (pin "3") (pinfunction "3_3") (pintype "bidirectional"))
      (node (ref "IC1") (pin "5V_ICSP") (pinfunction "5V_ICSP_5V_ICSP") (pintype "bidirectional"))
      (node (ref "IC1") (pin "GND1") (pinfunction "GND1_GND1") (pintype "bidirectional"))
      (node (ref "IC1") (pin "GND_1") (pinfunction "GND_1_GND_1") (pintype "bidirectional"))
      (node (ref "IC1") (pin "GND_2") (pinfunction "GND_2_GND_2") (pintype "bidirectional"))
      (node (ref "IC1") (pin "GND_A") (pinfunction "GND_A_GND_A") (pintype "bidirectional"))
      (node (ref "IC1") (pin "GND_B") (pinfunction "GND_B_GND_B") (pintype "bidirectional"))
      (node (ref "IC2") (pin "2") (pinfunction "GND_2") (pintype "passive"))
      (node (ref "IC3") (pin "2") (pinfunction "GND_2") (pintype "bidirectional"))
      (node (ref "IC3") (pin "8") (pinfunction "RS_8") (pintype "bidirectional"))
      (node (ref "IC4") (pin "2") (pinfunction "GND_2") (pintype "bidirectional"))
      (node (ref "IC4") (pin "8") (pinfunction "RS_8") (pintype "bidirectional"))
      (node (ref "IC5") (pin "2") (pinfunction "GND_2") (pintype "passive"))
      (node (ref "IC7") (pin "1") (pinfunction "A0_1") (pintype "input"))
      (node (ref "IC7") (pin "2") (pinfunction "A1_2") (pintype "input"))
      (node (ref "IC7") (pin "3") (pinfunction "A2_3") (pintype "input"))
      (node (ref "IC7") (pin "4") (pinfunction "GND_4") (pintype "power_in"))
      (node (ref "IC7") (pin "7") (pinfunction "WP_7") (pintype "input"))
      (node (ref "IC8") (pin "4") (pinfunction "P$4_4") (pintype "bidirectional"))
      (node (ref "J-AN1") (pin "3") (pinfunction "3_3") (pintype "bidirectional"))
      (node (ref "J-AN2") (pin "3") (pinfunction "3_3") (pintype "bidirectional"))
      (node (ref "J-AN3") (pin "3") (pinfunction "3_3") (pintype "bidirectional"))
      (node (ref "J-LEAF") (pin "1") (pinfunction "1_1") (pintype "passive"))
      (node (ref "J-LEAF") (pin "6") (pinfunction "6_6") (pintype "passive"))
      (node (ref "LCD") (pin "1") (pinfunction "1_1") (pintype "passive"))
      (node (ref "O1") (pin "3") (pinfunction "EMIT_3") (pintype "passive"))
      (node (ref "O2") (pin "3") (pinfunction "EMIT_3") (pintype "passive"))
      (node (ref "O3") (pin "3") (pinfunction "EMIT_3") (pintype "passive"))
      (node (ref "O4") (pin "2") (pinfunction "C_2") (pintype "passive"))
      (node (ref "O5") (pin "2") (pinfunction "C_2") (pintype "passive"))
      (node (ref "O6") (pin "2") (pinfunction "C_2") (pintype "passive"))
      (node (ref "O7") (pin "2") (pinfunction "C_2") (pintype "passive"))
      (node (ref "O8") (pin "2") (pinfunction "C_2") (pintype "passive"))
      (node (ref "O8") (pin "3") (pinfunction "EMIT_3") (pintype "passive"))
      (node (ref "O9") (pin "2") (pinfunction "C_2") (pintype "passive"))
      (node (ref "O9") (pin "3") (pinfunction "EMIT_3") (pintype "passive"))
      (node (ref "R23") (pin "P$1") (pinfunction "1_P$1") (pintype "passive"))
      (node (ref "R25") (pin "P$1") (pinfunction "1_P$1") (pintype "passive"))
      (node (ref "R28") (pin "P$1") (pinfunction "1_P$1") (pintype "passive"))
      (node (ref "SJ1") (pin "1") (pinfunction "1_1") (pintype "passive"))
      (node (ref "TB-12V") (pin "2") (pinfunction "2_2") (pintype "bidirectional"))
      (node (ref "TB1") (pin "3") (pinfunction "3_3") (pintype "bidirectional"))
      (node (ref "TP1") (pin "3") (pinfunction "P$3_3") (pintype "bidirectional"))
    )
    (net (code "15") (name "GNDI") (class "Default")
      (node (ref "J-BRAKE") (pin "2") (pinfunction "2_2") (pintype "bidirectional"))
      (node (ref "O1") (pin "2") (pinfunction "C_2") (pintype "passive"))
      (node (ref "O2") (pin "2") (pinfunction "C_2") (pintype "passive"))
      (node (ref "O3") (pin "2") (pinfunction "C_2") (pintype "passive"))
      (node (ref "Q1") (pin "S") (pinfunction "S_S") (pintype "passive"))
      (node (ref "Q2") (pin "S") (pinfunction "S_S") (pintype "passive"))
      (node (ref "Q3") (pin "S") (pinfunction "S_S") (pintype "passive"))
      (node (ref "R17") (pin "P$2") (pinfunction "2_P$2") (pintype "passive"))
      (node (ref "R19") (pin "P$2") (pinfunction "2_P$2") (pintype "passive"))
      (node (ref "R21") (pin "P$2") (pinfunction "2_P$2") (pintype "passive"))
      (node (ref "R33") (pin "P$1") (pinfunction "1_P$1") (pintype "passive"))
      (node (ref "SJ1") (pin "2") (pinfunction "2_2") (pintype "passive"))
      (node (ref "TB2") (pin "3") (pinfunction "3_3") (pintype "bidirectional"))
      (node (ref "TB3") (pin "2") (pinfunction "2_2") (pintype "bidirectional"))
      (node (ref "TB6") (pin "3") (pinfunction "3_3") (pintype "bidirectional"))
      (node (ref "TB7") (pin "2") (pinfunction "2_2") (pintype "bidirectional"))
    )
    (net (code "16") (name "IN-BRAKE") (class "Default")
      (node (ref "IC1") (pin "5") (pinfunction "5_5") (pintype "bidirectional"))
      (node (ref "IC1") (pin "A7") (pinfunction "A7_A7") (pintype "bidirectional"))
      (node (ref "O1") (pin "4") (pinfunction "COL_4") (pintype "passive"))
      (node (ref "R4") (pin "P$1") (pinfunction "1_P$1") (pintype "passive"))
    )
    (net (code "17") (name "IN1") (class "Default")
      (node (ref "R2") (pin "P$1") (pinfunction "1_P$1") (pintype "passive"))
      (node (ref "TB5") (pin "1") (pinfunction "1_1") (pintype "bidirectional"))
    )
    (net (code "18") (name "IN2") (class "Default")
      (node (ref "R3") (pin "P$1") (pinfunction "1_P$1") (pintype "passive"))
      (node (ref "TB5") (pin "2") (pinfunction "2_2") (pintype "bidirectional"))
    )
    (net (code "19") (name "INPUT1") (class "Default")
      (node (ref "IC1") (pin "6") (pinfunction "6_6") (pintype "bidirectional"))
      (node (ref "O2") (pin "4") (pinfunction "COL_4") (pintype "passive"))
      (node (ref "R5") (pin "P$1") (pinfunction "1_P$1") (pintype "passive"))
    )
    (net (code "20") (name "INPUT2") (class "Default")
      (node (ref "IC1") (pin "7") (pinfunction "7_7") (pintype "bidirectional"))
      (node (ref "O3") (pin "4") (pinfunction "COL_4") (pintype "passive"))
      (node (ref "R6") (pin "P$1") (pinfunction "1_P$1") (pintype "passive"))
    )
    (net (code "21") (name "MISO") (class "Default")
      (node (ref "IC1") (pin "MISO_ICSP") (pinfunction "MISO_ICSP_MISO_ICSP") (pintype "bidirectional"))
      (node (ref "IC8") (pin "2") (pinfunction "P$2_2") (pintype "bidirectional"))
      (node (ref "R26") (pin "1") (pinfunction "1_1") (pintype "passive"))
    )
    (net (code "22") (name "MOSI") (class "Default")
      (node (ref "IC1") (pin "MOSI_ICSP") (pinfunction "MOSI_ICSP_MOSI_ICSP") (pintype "bidirectional"))
      (node (ref "IC8") (pin "5") (pinfunction "P$5_5") (pintype "bidirectional"))
    )
    (net (code "23") (name "Net-(D5-PadA)") (class "Default")
      (node (ref "D5") (pin "A") (pinfunction "A_A") (pintype "passive"))
      (node (ref "D8") (pin "A") (pinfunction "A_A") (pintype "passive"))
      (node (ref "TB-12V") (pin "1") (pinfunction "1_1") (pintype "bidirectional"))
    )
    (net (code "24") (name "Net-(IC4-CANH)") (class "Default")
      (node (ref "IC4") (pin "7") (pinfunction "CANH_7") (pintype "bidirectional"))
      (node (ref "R10") (pin "P$2") (pinfunction "2_P$2") (pintype "passive"))
      (node (ref "TB1") (pin "1") (pinfunction "1_1") (pintype "bidirectional"))
    )
    (net (code "25") (name "Net-(IC4-CANL)") (class "Default")
      (node (ref "IC4") (pin "6") (pinfunction "CANL_6") (pintype "bidirectional"))
      (node (ref "R9") (pin "P$2") (pinfunction "2_P$2") (pintype "passive"))
      (node (ref "TB1") (pin "2") (pinfunction "2_2") (pintype "bidirectional"))
    )
    (net (code "26") (name "Net-(O1-A)") (class "Default")
      (node (ref "O1") (pin "1") (pinfunction "A_1") (pintype "passive"))
      (node (ref "R1") (pin "P$2") (pinfunction "2_P$2") (pintype "passive"))
    )
    (net (code "27") (name "Net-(O2-A)") (class "Default")
      (node (ref "O2") (pin "1") (pinfunction "A_1") (pintype "passive"))
      (node (ref "R2") (pin "P$2") (pinfunction "2_P$2") (pintype "passive"))
    )
    (net (code "28") (name "Net-(O3-A)") (class "Default")
      (node (ref "O3") (pin "1") (pinfunction "A_1") (pintype "passive"))
      (node (ref "R3") (pin "P$2") (pinfunction "2_P$2") (pintype "passive"))
    )
    (net (code "29") (name "Net-(O4-A)") (class "Default")
      (node (ref "O4") (pin "1") (pinfunction "A_1") (pintype "passive"))
      (node (ref "R13") (pin "P$2") (pinfunction "2_P$2") (pintype "passive"))
    )
    (net (code "30") (name "Net-(O4-EMIT)") (class "Default")
      (node (ref "O4") (pin "3") (pinfunction "EMIT_3") (pintype "passive"))
      (node (ref "R16") (pin "P$1") (pinfunction "1_P$1") (pintype "passive"))
    )
    (net (code "31") (name "Net-(O5-A)") (class "Default")
      (node (ref "O5") (pin "1") (pinfunction "A_1") (pintype "passive"))
      (node (ref "R14") (pin "P$2") (pinfunction "2_P$2") (pintype "passive"))
    )
    (net (code "32") (name "Net-(O5-EMIT)") (class "Default")
      (node (ref "O5") (pin "3") (pinfunction "EMIT_3") (pintype "passive"))
      (node (ref "R18") (pin "P$1") (pinfunction "1_P$1") (pintype "passive"))
    )
    (net (code "33") (name "Net-(O6-A)") (class "Default")
      (node (ref "O6") (pin "1") (pinfunction "A_1") (pintype "passive"))
      (node (ref "R15") (pin "P$2") (pinfunction "2_P$2") (pintype "passive"))
    )
    (net (code "34") (name "Net-(O6-EMIT)") (class "Default")
      (node (ref "O6") (pin "3") (pinfunction "EMIT_3") (pintype "passive"))
      (node (ref "R20") (pin "P$1") (pinfunction "1_P$1") (pintype "passive"))
    )
    (net (code "35") (name "Net-(O7-A)") (class "Default")
      (node (ref "O7") (pin "1") (pinfunction "A_1") (pintype "passive"))
      (node (ref "R34") (pin "P$2") (pinfunction "2_P$2") (pintype "passive"))
    )
    (net (code "36") (name "Net-(O7-COL)") (class "Default")
      (node (ref "JP1") (pin "2") (pinfunction "2_2") (pintype "bidirectional"))
      (node (ref "O7") (pin "4") (pinfunction "COL_4") (pintype "passive"))
    )
    (net (code "37") (name "Net-(O7-EMIT)") (class "Default")
      (node (ref "O7") (pin "3") (pinfunction "EMIT_3") (pintype "passive"))
      (node (ref "R33") (pin "P$2") (pinfunction "2_P$2") (pintype "passive"))
      (node (ref "TB2") (pin "2") (pinfunction "2_2") (pintype "bidirectional"))
    )
    (net (code "38") (name "Net-(O8-A)") (class "Default")
      (node (ref "O8") (pin "1") (pinfunction "A_1") (pintype "passive"))
      (node (ref "R36") (pin "P$2") (pinfunction "2_P$2") (pintype "passive"))
    )
    (net (code "39") (name "Net-(O8-COL)") (class "Default")
      (node (ref "O8") (pin "4") (pinfunction "COL_4") (pintype "passive"))
      (node (ref "R32") (pin "P$1") (pinfunction "1_P$1") (pintype "passive"))
    )
    (net (code "40") (name "Net-(O9-A)") (class "Default")
      (node (ref "O9") (pin "1") (pinfunction "A_1") (pintype "passive"))
      (node (ref "R35") (pin "P$2") (pinfunction "2_P$2") (pintype "passive"))
    )
    (net (code "41") (name "Net-(O9-COL)") (class "Default")
      (node (ref "O9") (pin "4") (pinfunction "COL_4") (pintype "passive"))
      (node (ref "R31") (pin "P$1") (pinfunction "1_P$1") (pintype "passive"))
    )
    (net (code "42") (name "Net-(Q4-PadD)") (class "Default")
      (node (ref "Q4") (pin "D") (pinfunction "D_D") (pintype "passive"))
      (node (ref "TB3") (pin "1") (pinfunction "1_1") (pintype "bidirectional"))
    )
    (net (code "43") (name "Net-(Q5-PadD)") (class "Default")
      (node (ref "Q5") (pin "D") (pinfunction "D_D") (pintype "passive"))
      (node (ref "TB2") (pin "1") (pinfunction "1_1") (pintype "bidirectional"))
    )
    (net (code "44") (name "Net-(R7-1)") (class "Default")
      (node (ref "C1") (pin "1") (pinfunction "1_1") (pintype "passive"))
      (node (ref "R7") (pin "P$1") (pinfunction "1_P$1") (pintype "passive"))
      (node (ref "R8") (pin "P$1") (pinfunction "1_P$1") (pintype "passive"))
    )
    (net (code "45") (name "Net-(R10-1)") (class "Default")
      (node (ref "C2") (pin "1") (pinfunction "1_1") (pintype "passive"))
      (node (ref "R10") (pin "P$1") (pinfunction "1_P$1") (pintype "passive"))
      (node (ref "R9") (pin "P$1") (pinfunction "1_P$1") (pintype "passive"))
    )
    (net (code "46") (name "Net-(R16-2)") (class "Default")
      (node (ref "Q1") (pin "G") (pinfunction "G_G") (pintype "passive"))
      (node (ref "R16") (pin "P$2") (pinfunction "2_P$2") (pintype "passive"))
      (node (ref "R17") (pin "P$1") (pinfunction "1_P$1") (pintype "passive"))
    )
    (net (code "47") (name "Net-(R18-2)") (class "Default")
      (node (ref "Q2") (pin "G") (pinfunction "G_G") (pintype "passive"))
      (node (ref "R18") (pin "P$2") (pinfunction "2_P$2") (pintype "passive"))
      (node (ref "R19") (pin "P$1") (pinfunction "1_P$1") (pintype "passive"))
    )
    (net (code "48") (name "Net-(R20-2)") (class "Default")
      (node (ref "Q3") (pin "G") (pinfunction "G_G") (pintype "passive"))
      (node (ref "R20") (pin "P$2") (pinfunction "2_P$2") (pintype "passive"))
      (node (ref "R21") (pin "P$1") (pinfunction "1_P$1") (pintype "passive"))
    )
    (net (code "49") (name "Net-(R27-1)") (class "Default")
      (node (ref "J-AN3") (pin "2") (pinfunction "2_2") (pintype "bidirectional"))
      (node (ref "R27") (pin "P$1") (pinfunction "1_P$1") (pintype "passive"))
      (node (ref "R28") (pin "P$2") (pinfunction "2_P$2") (pintype "passive"))
    )
    (net (code "50") (name "Net-(R29-2)") (class "Default")
      (node (ref "Q4") (pin "G") (pinfunction "G_G") (pintype "passive"))
      (node (ref "R29") (pin "P$2") (pinfunction "2_P$2") (pintype "passive"))
      (node (ref "R31") (pin "P$2") (pinfunction "2_P$2") (pintype "passive"))
    )
    (net (code "51") (name "Net-(R30-2)") (class "Default")
      (node (ref "Q5") (pin "G") (pinfunction "G_G") (pintype "passive"))
      (node (ref "R30") (pin "P$2") (pinfunction "2_P$2") (pintype "passive"))
      (node (ref "R32") (pin "P$2") (pinfunction "2_P$2") (pintype "passive"))
    )
    (net (code "52") (name "Net-(TP1-P$1)") (class "Default")
      (node (ref "IC1") (pin "A3") (pinfunction "A3_A3") (pintype "bidirectional"))
      (node (ref "TP1") (pin "1") (pinfunction "P$1_1") (pintype "bidirectional"))
    )
    (net (code "53") (name "Net-(TP1-P$2)") (class "Default")
      (node (ref "IC1") (pin "A4") (pinfunction "A4_A4") (pintype "bidirectional"))
      (node (ref "TP1") (pin "2") (pinfunction "P$2_2") (pintype "bidirectional"))
    )
    (net (code "54") (name "OP1") (class "Default")
      (node (ref "Q1") (pin "D") (pinfunction "D_D") (pintype "passive"))
      (node (ref "TB6") (pin "1") (pinfunction "1_1") (pintype "bidirectional"))
    )
    (net (code "55") (name "OP2") (class "Default")
      (node (ref "Q2") (pin "D") (pinfunction "D_D") (pintype "passive"))
      (node (ref "TB6") (pin "2") (pinfunction "2_2") (pintype "bidirectional"))
    )
    (net (code "56") (name "OP3") (class "Default")
      (node (ref "Q3") (pin "D") (pinfunction "D_D") (pintype "passive"))
      (node (ref "TB7") (pin "1") (pinfunction "1_1") (pintype "bidirectional"))
    )
    (net (code "57") (name "OUT1") (class "Default")
      (node (ref "IC1") (pin "48") (pinfunction "48_48") (pintype "bidirectional"))
      (node (ref "R13") (pin "P$1") (pinfunction "1_P$1") (pintype "passive"))
    )
    (net (code "58") (name "OUT2") (class "Default")
      (node (ref "IC1") (pin "49") (pinfunction "49_49") (pintype "bidirectional"))
      (node (ref "R14") (pin "P$1") (pinfunction "1_P$1") (pintype "passive"))
    )
    (net (code "59") (name "OUT3") (class "Default")
      (node (ref "IC1") (pin "50") (pinfunction "50_50") (pintype "bidirectional"))
      (node (ref "R15") (pin "P$1") (pinfunction "1_P$1") (pintype "passive"))
    )
    (net (code "60") (name "OUT4") (class "Default")
      (node (ref "IC1") (pin "51") (pinfunction "51_51") (pintype "bidirectional"))
      (node (ref "R35") (pin "P$1") (pinfunction "1_P$1") (pintype "passive"))
    )
    (net (code "61") (name "OUT5") (class "Default")
      (node (ref "IC1") (pin "52") (pinfunction "52_52") (pintype "bidirectional"))
      (node (ref "R36") (pin "P$1") (pinfunction "1_P$1") (pintype "passive"))
    )
    (net (code "62") (name "PTCANH") (class "Default")
      (node (ref "IC3") (pin "7") (pinfunction "CANH_7") (pintype "bidirectional"))
      (node (ref "J-LEAF") (pin "4") (pinfunction "4_4") (pintype "passive"))
      (node (ref "R8") (pin "P$2") (pinfunction "2_P$2") (pintype "passive"))
    )
    (net (code "63") (name "PTCANL") (class "Default")
      (node (ref "IC3") (pin "6") (pinfunction "CANL_6") (pintype "bidirectional"))
      (node (ref "J-LEAF") (pin "5") (pinfunction "5_5") (pintype "passive"))
      (node (ref "R7") (pin "P$2") (pinfunction "2_P$2") (pintype "passive"))
    )
    (net (code "64") (name "PWM") (class "Default")
      (node (ref "IC1") (pin "9") (pinfunction "9_9") (pintype "bidirectional"))
      (node (ref "R34") (pin "P$1") (pinfunction "1_P$1") (pintype "passive"))
    )
    (net (code "65") (name "RX2") (class "Default")
      (node (ref "ESP8266") (pin "7") (pinfunction "7_7") (pintype "bidirectional"))
      (node (ref "IC1") (pin "RX2") (pinfunction "RX2_RX2") (pintype "bidirectional"))
    )
    (net (code "66") (name "SCK") (class "Default")
      (node (ref "IC1") (pin "SCK_ICSP") (pinfunction "SCK_ICSP_SCK_ICSP") (pintype "bidirectional"))
      (node (ref "IC8") (pin "6") (pinfunction "P$6_6") (pintype "bidirectional"))
    )
    (net (code "67") (name "SCL") (class "Default")
      (node (ref "IC1") (pin "SCL") (pinfunction "SCL_SCL") (pintype "bidirectional"))
      (node (ref "IC7") (pin "6") (pinfunction "SCL_6") (pintype "input"))
      (node (ref "LCD") (pin "4") (pinfunction "4_4") (pintype "passive"))
      (node (ref "R12") (pin "P$1") (pinfunction "1_P$1") (pintype "passive"))
    )
    (net (code "68") (name "SDA") (class "Default")
      (node (ref "IC1") (pin "SDA") (pinfunction "SDA_SDA") (pintype "bidirectional"))
      (node (ref "IC7") (pin "5") (pinfunction "SDA_5") (pintype "bidirectional"))
      (node (ref "LCD") (pin "3") (pinfunction "3_3") (pintype "passive"))
      (node (ref "R11") (pin "P$1") (pinfunction "1_P$1") (pintype "passive"))
    )
    (net (code "69") (name "THROTTLE1") (class "Default")
      (node (ref "J-AN1") (pin "2") (pinfunction "2_2") (pintype "bidirectional"))
      (node (ref "R22") (pin "P$1") (pinfunction "1_P$1") (pintype "passive"))
    )
    (net (code "70") (name "THROTTLE2") (class "Default")
      (node (ref "J-AN2") (pin "2") (pinfunction "2_2") (pintype "bidirectional"))
      (node (ref "R24") (pin "P$1") (pinfunction "1_P$1") (pintype "passive"))
    )
    (net (code "71") (name "TX2") (class "Default")
      (node (ref "ESP8266") (pin "5") (pinfunction "5_5") (pintype "bidirectional"))
      (node (ref "IC1") (pin "TX2") (pinfunction "TX2_TX2") (pintype "bidirectional"))
    )
    (net (code "72") (name "unconnected-(ESP8266-Pad2)") (class "Default")
      (node (ref "ESP8266") (pin "2") (pinfunction "2_2") (pintype "bidirectional"))
    )
    (net (code "73") (name "unconnected-(ESP8266-Pad4)") (class "Default")
      (node (ref "ESP8266") (pin "4") (pinfunction "4_4") (pintype "bidirectional"))
    )
    (net (code "74") (name "unconnected-(ESP8266-Pad6)") (class "Default")
      (node (ref "ESP8266") (pin "6") (pinfunction "6_6") (pintype "bidirectional"))
    )
    (net (code "75") (name "unconnected-(ESP8266-Pad8)") (class "Default")
      (node (ref "ESP8266") (pin "8") (pinfunction "8_8") (pintype "bidirectional"))
    )
    (net (code "76") (name "unconnected-(ESP8266-Pad9)") (class "Default")
      (node (ref "ESP8266") (pin "9") (pinfunction "9_9") (pintype "bidirectional"))
    )
    (net (code "77") (name "unconnected-(ESP8266-Pad10)") (class "Default")
      (node (ref "ESP8266") (pin "10") (pinfunction "10_10") (pintype "bidirectional"))
    )
    (net (code "78") (name "unconnected-(IC1-Pad3)") (class "Default")
      (node (ref "IC1") (pin "3") (pinfunction "3_3") (pintype "bidirectional"))
    )
    (net (code "79") (name "unconnected-(IC1-Pad4)") (class "Default")
      (node (ref "IC1") (pin "4") (pinfunction "4_4") (pintype "bidirectional"))
    )
    (net (code "80") (name "unconnected-(IC1-Pad5V)") (class "Default")
      (node (ref "IC1") (pin "5V") (pinfunction "5V_5V") (pintype "bidirectional"))
    )
    (net (code "81") (name "unconnected-(IC1-Pad5V_A)") (class "Default")
      (node (ref "IC1") (pin "5V_A") (pinfunction "5V_A_5V_A") (pintype "bidirectional"))
    )
    (net (code "82") (name "unconnected-(IC1-Pad5V_B)") (class "Default")
      (node (ref "IC1") (pin "5V_B") (pinfunction "5V_B_5V_B") (pintype "bidirectional"))
    )
    (net (code "83") (name "unconnected-(IC1-Pad8)") (class "Default")
      (node (ref "IC1") (pin "8") (pinfunction "8_8") (pintype "bidirectional"))
    )
    (net (code "84") (name "unconnected-(IC1-Pad10)") (class "Default")
      (node (ref "IC1") (pin "10") (pinfunction "10_10") (pintype "bidirectional"))
    )
    (net (code "85") (name "unconnected-(IC1-Pad11)") (class "Default")
      (node (ref "IC1") (pin "11") (pinfunction "11_11") (pintype "bidirectional"))
    )
    (net (code "86") (name "unconnected-(IC1-Pad12)") (class "Default")
      (node (ref "IC1") (pin "12") (pinfunction "12_12") (pintype "bidirectional"))
    )
    (net (code "87") (name "unconnected-(IC1-Pad13)") (class "Default")
      (node (ref "IC1") (pin "13") (pinfunction "13_13") (pintype "bidirectional"))
    )
    (net (code "88") (name "unconnected-(IC1-Pad22)") (class "Default")
      (node (ref "IC1") (pin "22") (pinfunction "22_22") (pintype "bidirectional"))
    )
    (net (code "89") (name "unconnected-(IC1-Pad23)") (class "Default")
      (node (ref "IC1") (pin "23") (pinfunction "23_23") (pintype "bidirectional"))
    )
    (net (code "90") (name "unconnected-(IC1-Pad24)") (class "Default")
      (node (ref "IC1") (pin "24") (pinfunction "24_24") (pintype "bidirectional"))
    )
    (net (code "91") (name "unconnected-(IC1-Pad25)") (class "Default")
      (node (ref "IC1") (pin "25") (pinfunction "25_25") (pintype "bidirectional"))
    )
    (net (code "92") (name "unconnected-(IC1-Pad26)") (class "Default")
      (node (ref "IC1") (pin "26") (pinfunction "26_26") (pintype "bidirectional"))
    )
    (net (code "93") (name "unconnected-(IC1-Pad27)") (class "Default")
      (node (ref "IC1") (pin "27") (pinfunction "27_27") (pintype "bidirectional"))
    )
    (net (code "94") (name "unconnected-(IC1-Pad28)") (class "Default")
      (node (ref "IC1") (pin "28") (pinfunction "28_28") (pintype "bidirectional"))
    )
    (net (code "95") (name "unconnected-(IC1-Pad29)") (class "Default")
      (node (ref "IC1") (pin "29") (pinfunction "29_29") (pintype "bidirectional"))
    )
    (net (code "96") (name "unconnected-(IC1-Pad30)") (class "Default")
      (node (ref "IC1") (pin "30") (pinfunction "30_30") (pintype "bidirectional"))
    )
    (net (code "97") (name "unconnected-(IC1-Pad31)") (class "Default")
      (node (ref "IC1") (pin "31") (pinfunction "31_31") (pintype "bidirectional"))
    )
    (net (code "98") (name "unconnected-(IC1-Pad32)") (class "Default")
      (node (ref "IC1") (pin "32") (pinfunction "32_32") (pintype "bidirectional"))
    )
    (net (code "99") (name "unconnected-(IC1-Pad33)") (class "Default")
      (node (ref "IC1") (pin "33") (pinfunction "33_33") (pintype "bidirectional"))
    )
    (net (code "100") (name "unconnected-(IC1-Pad34)") (class "Default")
      (node (ref "IC1") (pin "34") (pinfunction "34_34") (pintype "bidirectional"))
    )
    (net (code "101") (name "unconnected-(IC1-Pad35)") (class "Default")
      (node (ref "IC1") (pin "35") (pinfunction "35_35") (pintype "bidirectional"))
    )
    (net (code "102") (name "unconnected-(IC1-Pad36)") (class "Default")
      (node (ref "IC1") (pin "36") (pinfunction "36_36") (pintype "bidirectional"))
    )
    (net (code "103") (name "unconnected-(IC1-Pad37)") (class "Default")
      (node (ref "IC1") (pin "37") (pinfunction "37_37") (pintype "bidirectional"))
    )
    (net (code "104") (name "unconnected-(IC1-Pad38)") (class "Default")
      (node (ref "IC1") (pin "38") (pinfunction "38_38") (pintype "bidirectional"))
    )
    (net (code "105") (name "unconnected-(IC1-Pad39)") (class "Default")
      (node (ref "IC1") (pin "39") (pinfunction "39_39") (pintype "bidirectional"))
    )
    (net (code "106") (name "unconnected-(IC1-Pad40)") (class "Default")
      (node (ref "IC1") (pin "40") (pinfunction "40_40") (pintype "bidirectional"))
    )
    (net (code "107") (name "unconnected-(IC1-Pad41)") (class "Default")
      (node (ref "IC1") (pin "41") (pinfunction "41_41") (pintype "bidirectional"))
    )
    (net (code "108") (name "unconnected-(IC1-Pad42)") (class "Default")
      (node (ref "IC1") (pin "42") (pinfunction "42_42") (pintype "bidirectional"))
    )
    (net (code "109") (name "unconnected-(IC1-Pad43)") (class "Default")
      (node (ref "IC1") (pin "43") (pinfunction "43_43") (pintype "bidirectional"))
    )
    (net (code "110") (name "unconnected-(IC1-Pad44)") (class "Default")
      (node (ref "IC1") (pin "44") (pinfunction "44_44") (pintype "bidirectional"))
    )
    (net (code "111") (name "unconnected-(IC1-Pad45)") (class "Default")
      (node (ref "IC1") (pin "45") (pinfunction "45_45") (pintype "bidirectional"))
    )
    (net (code "112") (name "unconnected-(IC1-Pad46)") (class "Default")
      (node (ref "IC1") (pin "46") (pinfunction "46_46") (pintype "bidirectional"))
    )
    (net (code "113") (name "unconnected-(IC1-Pad47)") (class "Default")
      (node (ref "IC1") (pin "47") (pinfunction "47_47") (pintype "bidirectional"))
    )
    (net (code "114") (name "unconnected-(IC1-PadA5)") (class "Default")
      (node (ref "IC1") (pin "A5") (pinfunction "A5_A5") (pintype "bidirectional"))
    )
    (net (code "115") (name "unconnected-(IC1-PadA6)") (class "Default")
      (node (ref "IC1") (pin "A6") (pinfunction "A6_A6") (pintype "bidirectional"))
    )
    (net (code "116") (name "unconnected-(IC1-PadA8)") (class "Default")
      (node (ref "IC1") (pin "A8") (pinfunction "A8_A8") (pintype "bidirectional"))
    )
    (net (code "117") (name "unconnected-(IC1-PadA9)") (class "Default")
      (node (ref "IC1") (pin "A9") (pinfunction "A9_A9") (pintype "bidirectional"))
    )
    (net (code "118") (name "unconnected-(IC1-PadA10)") (class "Default")
      (node (ref "IC1") (pin "A10") (pinfunction "A10_A10") (pintype "bidirectional"))
    )
    (net (code "119") (name "unconnected-(IC1-PadA11)") (class "Default")
      (node (ref "IC1") (pin "A11") (pinfunction "A11_A11") (pintype "bidirectional"))
    )
    (net (code "120") (name "unconnected-(IC1-PadAREF)") (class "Default")
      (node (ref "IC1") (pin "AREF") (pinfunction "AREF_AREF") (pintype "bidirectional"))
    )
    (net (code "121") (name "unconnected-(IC1-PadDAC1)") (class "Default")
      (node (ref "IC1") (pin "DAC1") (pinfunction "DAC1_DAC1") (pintype "bidirectional"))
    )
    (net (code "122") (name "unconnected-(IC1-PadGND_DEBUG)") (class "Default")
      (node (ref "IC1") (pin "GND_DEBUG") (pinfunction "GND_DEBUG_GND_DEBUG") (pintype "bidirectional"))
    )
    (net (code "123") (name "unconnected-(IC1-PadGND_ICSP)") (class "Default")
      (node (ref "IC1") (pin "GND_ICSP") (pinfunction "GND_ICSP_GND_ICSP") (pintype "bidirectional"))
    )
    (net (code "124") (name "unconnected-(IC1-PadIOREF)") (class "Default")
      (node (ref "IC1") (pin "IOREF") (pinfunction "IOREF_IOREF") (pintype "bidirectional"))
    )
    (net (code "125") (name "unconnected-(IC1-PadNC)") (class "Default")
      (node (ref "IC1") (pin "NC") (pinfunction "NC_NC") (pintype "bidirectional"))
    )
    (net (code "126") (name "unconnected-(IC1-PadRESET)") (class "Default")
      (node (ref "IC1") (pin "RESET") (pinfunction "RESET_RESET") (pintype "bidirectional"))
    )
    (net (code "127") (name "unconnected-(IC1-PadRESET_DEBUG)") (class "Default")
      (node (ref "IC1") (pin "RESET_DEBUG") (pinfunction "RESET_DEBUG_RESET_DEBUG") (pintype "bidirectional"))
    )
    (net (code "128") (name "unconnected-(IC1-PadRESET_ICSP)") (class "Default")
      (node (ref "IC1") (pin "RESET_ICSP") (pinfunction "RESET_ICSP_RESET_ICSP") (pintype "bidirectional"))
    )
    (net (code "129") (name "unconnected-(IC1-PadRX0)") (class "Default")
      (node (ref "IC1") (pin "RX0") (pinfunction "RX0_RX0") (pintype "bidirectional"))
    )
    (net (code "130") (name "unconnected-(IC1-PadRX1)") (class "Default")
      (node (ref "IC1") (pin "RX1") (pinfunction "RX1_RX1") (pintype "bidirectional"))
    )
    (net (code "131") (name "unconnected-(IC1-PadRX3)") (class "Default")
      (node (ref "IC1") (pin "RX3") (pinfunction "RX3_RX3") (pintype "bidirectional"))
    )
    (net (code "132") (name "unconnected-(IC1-PadSCL1)") (class "Default")
      (node (ref "IC1") (pin "SCL1") (pinfunction "SCL1_SCL1") (pintype "bidirectional"))
    )
    (net (code "133") (name "unconnected-(IC1-PadSDA1)") (class "Default")
      (node (ref "IC1") (pin "SDA1") (pinfunction "SDA1_SDA1") (pintype "bidirectional"))
    )
    (net (code "134") (name "unconnected-(IC1-PadSWCLK_DEBUG)") (class "Default")
      (node (ref "IC1") (pin "SWCLK_DEBUG") (pinfunction "SWCLK_DEBUG_SWCLK_DEBUG") (pintype "bidirectional"))
    )
    (net (code "135") (name "unconnected-(IC1-PadSWDIO_DEBUG)") (class "Default")
      (node (ref "IC1") (pin "SWDIO_DEBUG") (pinfunction "SWDIO_DEBUG_SWDIO_DEBUG") (pintype "bidirectional"))
    )
    (net (code "136") (name "unconnected-(IC1-PadTX0)") (class "Default")
      (node (ref "IC1") (pin "TX0") (pinfunction "TX0_TX0") (pintype "bidirectional"))
    )
    (net (code "137") (name "unconnected-(IC1-PadTX1)") (class "Default")
      (node (ref "IC1") (pin "TX1") (pinfunction "TX1_TX1") (pintype "bidirectional"))
    )
    (net (code "138") (name "unconnected-(IC1-PadTX3)") (class "Default")
      (node (ref "IC1") (pin "TX3") (pinfunction "TX3_TX3") (pintype "bidirectional"))
    )
    (net (code "139") (name "unconnected-(IC8-P$3-Pad3)") (class "Default")
      (node (ref "IC8") (pin "3") (pinfunction "P$3_3") (pintype "bidirectional"))
    )
    (net (code "140") (name "unconnected-(IC8-P$7-Pad7)") (class "Default")
      (node (ref "IC8") (pin "7") (pinfunction "P$7_7") (pintype "bidirectional"))
    )
  )
)
